# schematic.net
KiCad netlist of a schematic drawn in EasyEDA
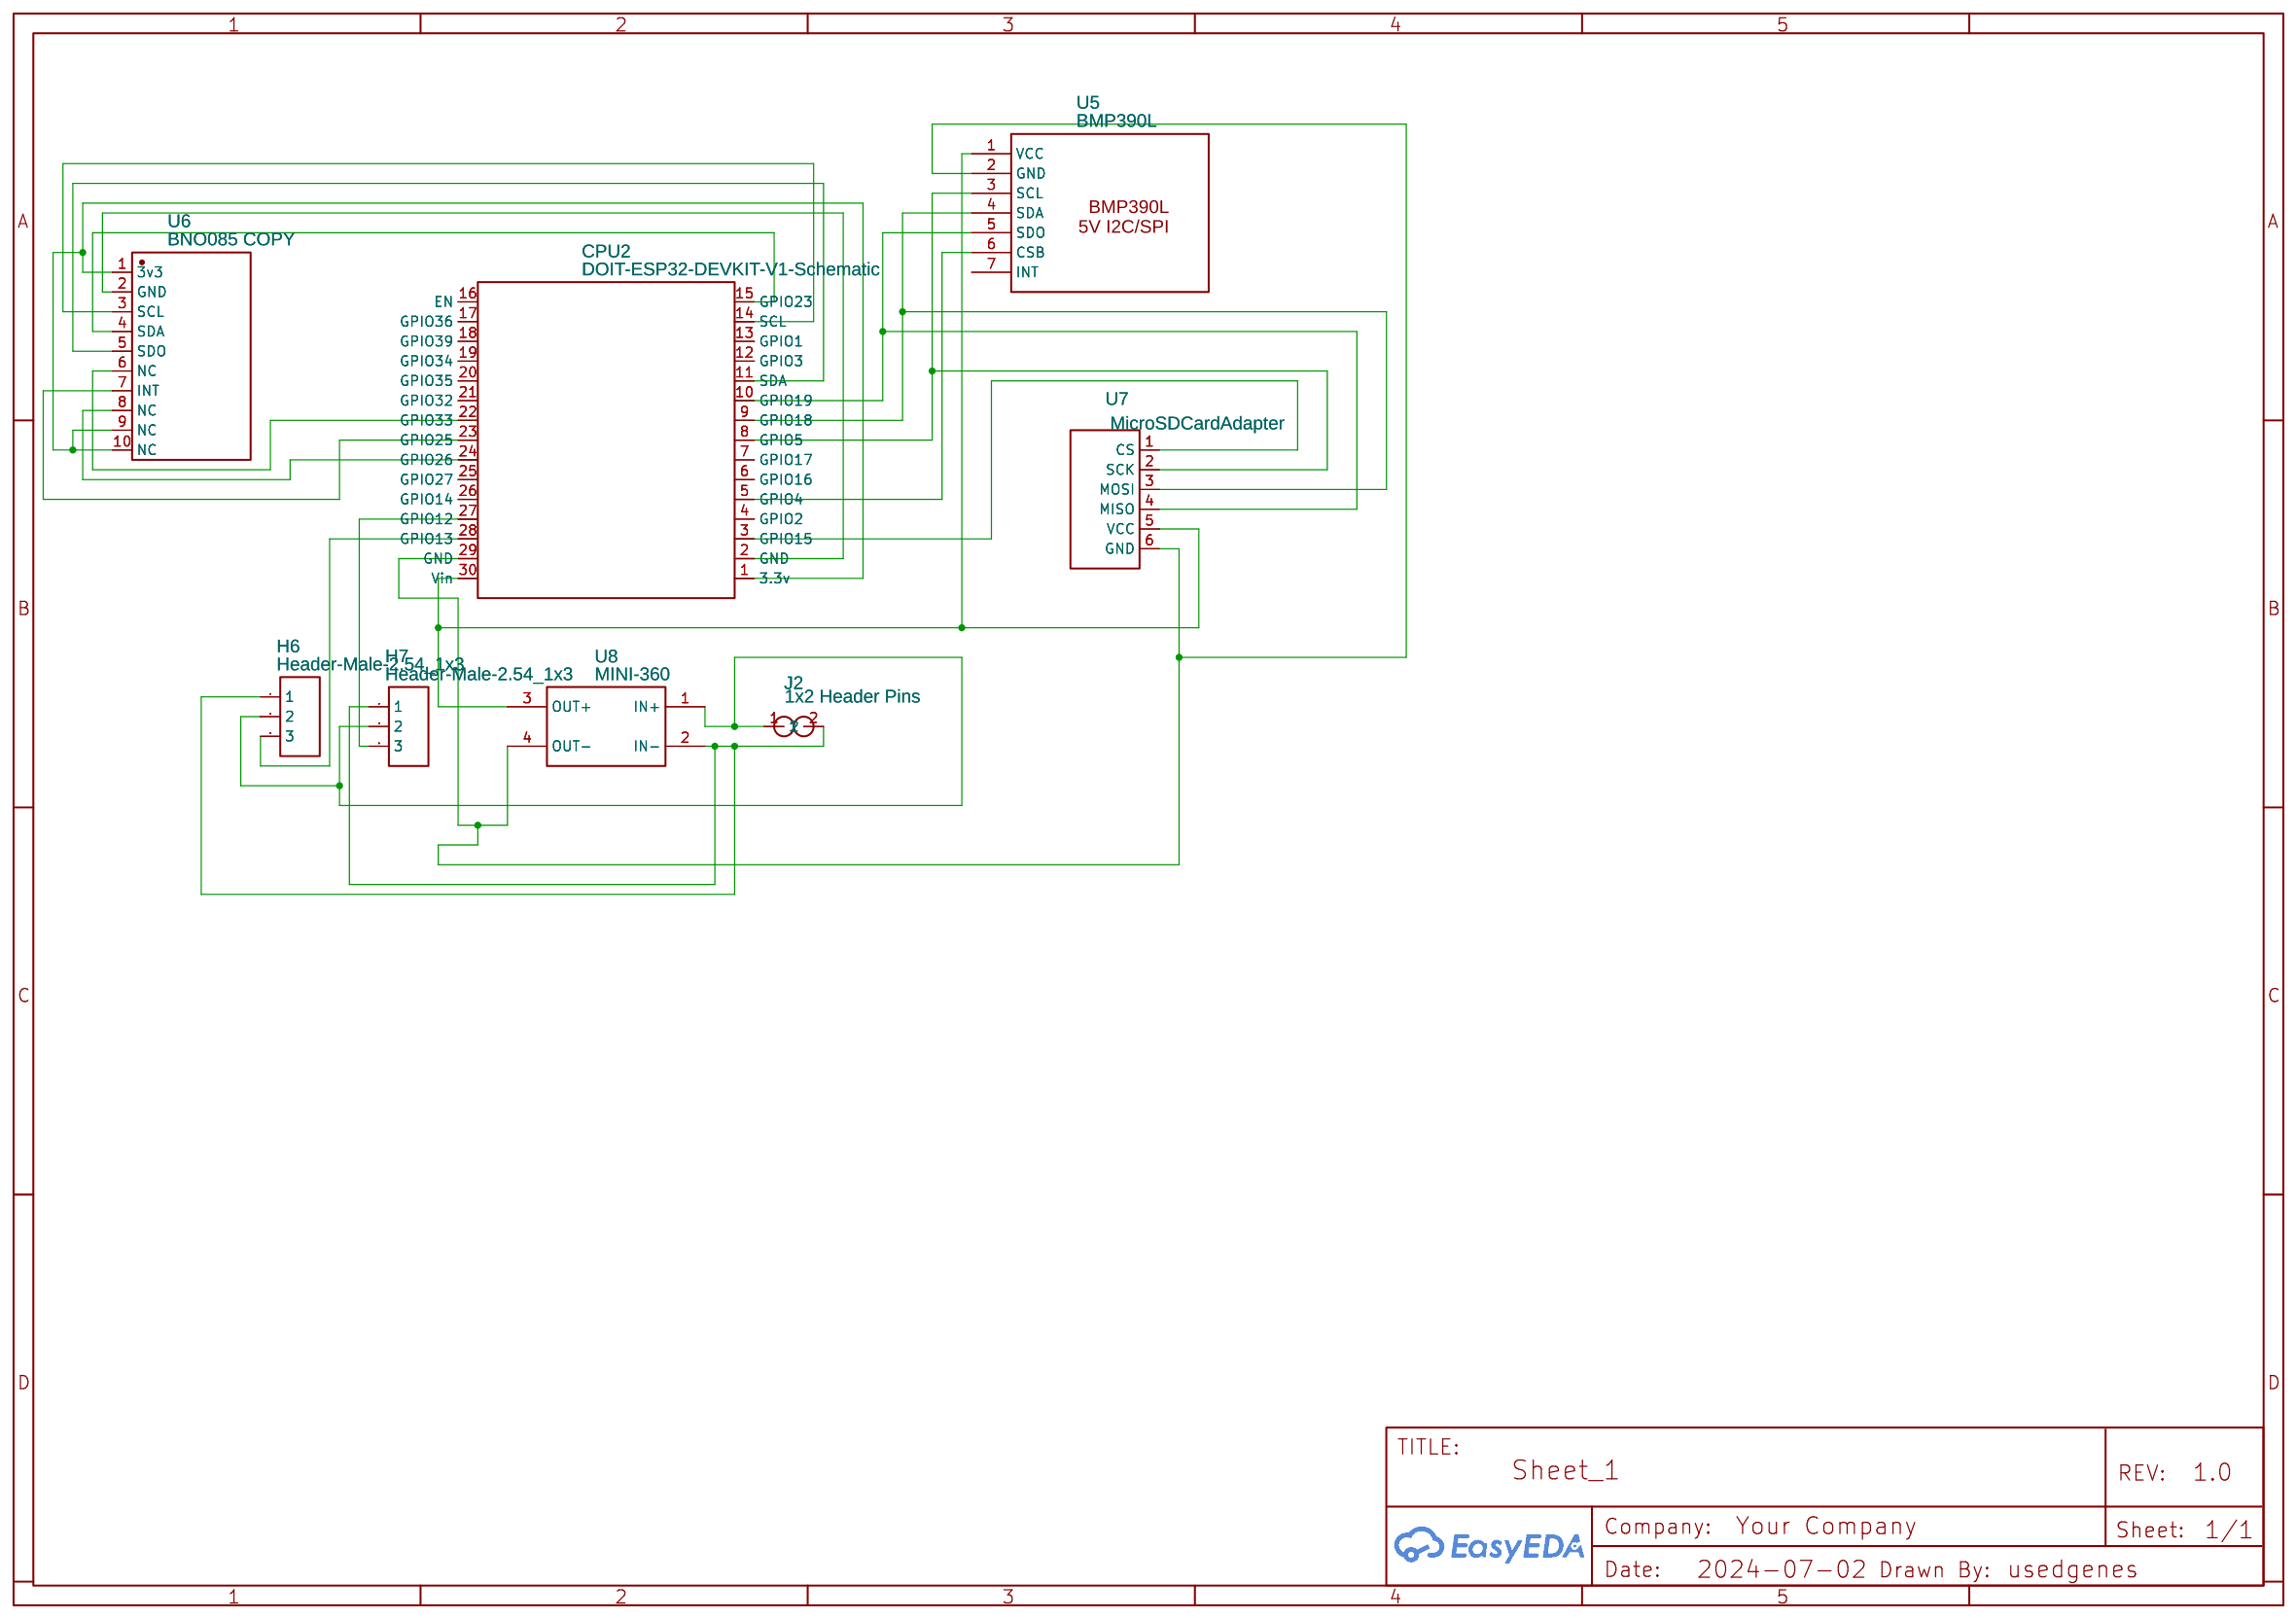
[diagram p0: schematic sheet]

(export (version "E")
  (design (tool "Eeschema 10.0.6"))
  (components
    (comp (ref "CPU2")
      (value "DOIT-ESP32-DEVKIT-V1-Schematic")
      (fields (field (name "Manufacturer Part") "NONE"))
      (libsource (lib "") (part "DOIT-ESP32-DEVKIT-V1-Schematic"))
    )
    (comp (ref "H6")
      (value "Header-Male-2.54_1x3")
      (fields (field (name "Manufacturer Part") "2.54-1*3P针") (field (name "Manufacturer") "BOOMELE(博穆精密)"))
      (libsource (lib "") (part "Header-Male-2.54_1x3"))
    )
    (comp (ref "H7")
      (value "Header-Male-2.54_1x3")
      (fields (field (name "Manufacturer Part") "2.54-1*3P针") (field (name "Manufacturer") "BOOMELE(博穆精密)"))
      (libsource (lib "") (part "Header-Male-2.54_1x3"))
    )
    (comp (ref "J2")
      (value "1x2 Header Pins")
      (fields
        (field (name "Manufacturer Part") "61300211121")
        (field (name "Manufacturer") "Wurth Electronics")
      )
      (libsource (lib "") (part "1x2 Header Pins"))
    )
    (comp (ref "U5")
      (value "BMP390L")
      (fields (field (name "Manufacturer Part") "BME280") (field (name "Manufacturer") "ditmore"))
      (libsource (lib "") (part "BMP390L"))
    )
    (comp (ref "U6")
      (value "BNO085 COPY")
      (fields (field (name "Manufacturer Part") "BNO085") (field (name "Manufacturer") "Slime"))
      (libsource (lib "") (part "BNO085 COPY"))
    )
    (comp (ref "U7") (value "MicroSDCardAdapter") (libsource (lib "") (part "MicroSDCardAdapter")))
    (comp (ref "U8") (value "MINI-360") (libsource (lib "") (part "MINI-360")))
  )
  (nets
    (net (code "1") (name "Net-(CPU2-3.3v)") (class "Default")
      (node (ref "CPU2") (pin "1") (pinfunction "3.3v_1") (pintype "unspecified"))
      (node (ref "U6") (pin "1") (pinfunction "3v3_1") (pintype "unspecified"))
      (node (ref "U6") (pin "10") (pinfunction "NC_10") (pintype "unspecified"))
      (node (ref "U6") (pin "9") (pinfunction "NC_9") (pintype "unspecified"))
    )
    (net (code "2") (name "Net-(CPU2-GPIO4)") (class "Default")
      (node (ref "CPU2") (pin "5") (pinfunction "GPIO4_5") (pintype "unspecified"))
      (node (ref "U5") (pin "6") (pinfunction "CSB_6") (pintype "unspecified"))
    )
    (net (code "3") (name "Net-(CPU2-GPIO5)") (class "Default")
      (node (ref "CPU2") (pin "8") (pinfunction "GPIO5_8") (pintype "unspecified"))
      (node (ref "U5") (pin "3") (pinfunction "SCL_3") (pintype "unspecified"))
      (node (ref "U7") (pin "2") (pinfunction "SCK_2") (pintype "bidirectional"))
    )
    (net (code "4") (name "Net-(CPU2-GPIO12)") (class "Default")
      (node (ref "CPU2") (pin "27") (pinfunction "GPIO12_27") (pintype "unspecified"))
      (node (ref "H7") (pin "3") (pinfunction "3_3") (pintype "input"))
    )
    (net (code "5") (name "Net-(CPU2-GPIO13)") (class "Default")
      (node (ref "CPU2") (pin "28") (pinfunction "GPIO13_28") (pintype "unspecified"))
      (node (ref "H6") (pin "3") (pinfunction "3_3") (pintype "input"))
    )
    (net (code "6") (name "Net-(CPU2-GPIO15)") (class "Default")
      (node (ref "CPU2") (pin "3") (pinfunction "GPIO15_3") (pintype "unspecified"))
      (node (ref "U7") (pin "1") (pinfunction "CS_1") (pintype "bidirectional"))
    )
    (net (code "7") (name "Net-(CPU2-GPIO18)") (class "Default")
      (node (ref "CPU2") (pin "9") (pinfunction "GPIO18_9") (pintype "unspecified"))
      (node (ref "U5") (pin "4") (pinfunction "SDA_4") (pintype "unspecified"))
      (node (ref "U7") (pin "3") (pinfunction "MOSI_3") (pintype "passive"))
    )
    (net (code "8") (name "Net-(CPU2-GPIO19)") (class "Default")
      (node (ref "CPU2") (pin "10") (pinfunction "GPIO19_10") (pintype "unspecified"))
      (node (ref "U5") (pin "5") (pinfunction "SDO_5") (pintype "unspecified"))
      (node (ref "U7") (pin "4") (pinfunction "MISO_4") (pintype "bidirectional"))
    )
    (net (code "9") (name "Net-(CPU2-GPIO23)") (class "Default")
      (node (ref "CPU2") (pin "15") (pinfunction "GPIO23_15") (pintype "unspecified"))
      (node (ref "U6") (pin "4") (pinfunction "SDA_4") (pintype "unspecified"))
    )
    (net (code "10") (name "Net-(CPU2-GPIO25)") (class "Default")
      (node (ref "CPU2") (pin "23") (pinfunction "GPIO25_23") (pintype "unspecified"))
      (node (ref "U6") (pin "7") (pinfunction "INT_7") (pintype "unspecified"))
    )
    (net (code "11") (name "Net-(CPU2-GPIO26)") (class "Default")
      (node (ref "CPU2") (pin "24") (pinfunction "GPIO26_24") (pintype "unspecified"))
      (node (ref "U6") (pin "8") (pinfunction "NC_8") (pintype "unspecified"))
    )
    (net (code "12") (name "Net-(CPU2-GPIO33)") (class "Default")
      (node (ref "CPU2") (pin "22") (pinfunction "GPIO33_22") (pintype "unspecified"))
      (node (ref "U6") (pin "6") (pinfunction "NC_6") (pintype "unspecified"))
    )
    (net (code "13") (name "Net-(CPU2-SCL)") (class "Default")
      (node (ref "CPU2") (pin "14") (pinfunction "SCL_14") (pintype "unspecified"))
      (node (ref "U6") (pin "3") (pinfunction "SCL_3") (pintype "unspecified"))
    )
    (net (code "14") (name "Net-(CPU2-SDA)") (class "Default")
      (node (ref "CPU2") (pin "11") (pinfunction "SDA_11") (pintype "unspecified"))
      (node (ref "U6") (pin "5") (pinfunction "SDO_5") (pintype "unspecified"))
    )
    (net (code "15") (name "Net-(CPU2-Vin)") (class "Default")
      (node (ref "CPU2") (pin "30") (pinfunction "Vin_30") (pintype "unspecified"))
      (node (ref "U5") (pin "1") (pinfunction "VCC_1") (pintype "unspecified"))
      (node (ref "U7") (pin "5") (pinfunction "VCC_5") (pintype "passive"))
      (node (ref "U8") (pin "3") (pinfunction "OUT+_3") (pintype "unspecified"))
    )
    (net (code "16") (name "Net-(U5-GND)") (class "Default")
      (node (ref "CPU2") (pin "29") (pinfunction "GND_29") (pintype "unspecified"))
      (node (ref "U5") (pin "2") (pinfunction "GND_2") (pintype "unspecified"))
      (node (ref "U7") (pin "6") (pinfunction "GND_6") (pintype "passive"))
      (node (ref "U8") (pin "4") (pinfunction "OUT-_4") (pintype "unspecified"))
    )
    (net (code "17") (name "Net-(U6-GND)") (class "Default")
      (node (ref "CPU2") (pin "2") (pinfunction "GND_2") (pintype "unspecified"))
      (node (ref "U6") (pin "2") (pinfunction "GND_2") (pintype "unspecified"))
    )
    (net (code "18") (name "Net-(U8-IN+)") (class "Default")
      (node (ref "H6") (pin "2") (pinfunction "2_2") (pintype "input"))
      (node (ref "H7") (pin "2") (pinfunction "2_2") (pintype "input"))
      (node (ref "J2") (pin "1") (pinfunction "1_1") (pintype "unspecified"))
      (node (ref "U8") (pin "1") (pinfunction "IN+_1") (pintype "unspecified"))
    )
    (net (code "19") (name "Net-(U8-IN-)") (class "Default")
      (node (ref "H6") (pin "1") (pinfunction "1_1") (pintype "input"))
      (node (ref "H7") (pin "1") (pinfunction "1_1") (pintype "input"))
      (node (ref "J2") (pin "2") (pinfunction "2_2") (pintype "unspecified"))
      (node (ref "U8") (pin "2") (pinfunction "IN-_2") (pintype "unspecified"))
    )
    (net (code "20") (name "unconnected-(CPU2-EN-Pad16)") (class "Default")
      (node (ref "CPU2") (pin "16") (pinfunction "EN_16") (pintype "unspecified"))
    )
    (net (code "21") (name "unconnected-(CPU2-GPIO1-Pad13)") (class "Default")
      (node (ref "CPU2") (pin "13") (pinfunction "GPIO1_13") (pintype "unspecified"))
    )
    (net (code "22") (name "unconnected-(CPU2-GPIO2-Pad4)") (class "Default")
      (node (ref "CPU2") (pin "4") (pinfunction "GPIO2_4") (pintype "unspecified"))
    )
    (net (code "23") (name "unconnected-(CPU2-GPIO3-Pad12)") (class "Default")
      (node (ref "CPU2") (pin "12") (pinfunction "GPIO3_12") (pintype "unspecified"))
    )
    (net (code "24") (name "unconnected-(CPU2-GPIO14-Pad26)") (class "Default")
      (node (ref "CPU2") (pin "26") (pinfunction "GPIO14_26") (pintype "unspecified"))
    )
    (net (code "25") (name "unconnected-(CPU2-GPIO16-Pad6)") (class "Default")
      (node (ref "CPU2") (pin "6") (pinfunction "GPIO16_6") (pintype "unspecified"))
    )
    (net (code "26") (name "unconnected-(CPU2-GPIO17-Pad7)") (class "Default")
      (node (ref "CPU2") (pin "7") (pinfunction "GPIO17_7") (pintype "unspecified"))
    )
    (net (code "27") (name "unconnected-(CPU2-GPIO27-Pad25)") (class "Default")
      (node (ref "CPU2") (pin "25") (pinfunction "GPIO27_25") (pintype "unspecified"))
    )
    (net (code "28") (name "unconnected-(CPU2-GPIO32-Pad21)") (class "Default")
      (node (ref "CPU2") (pin "21") (pinfunction "GPIO32_21") (pintype "unspecified"))
    )
    (net (code "29") (name "unconnected-(CPU2-GPIO34-Pad19)") (class "Default")
      (node (ref "CPU2") (pin "19") (pinfunction "GPIO34_19") (pintype "unspecified"))
    )
    (net (code "30") (name "unconnected-(CPU2-GPIO35-Pad20)") (class "Default")
      (node (ref "CPU2") (pin "20") (pinfunction "GPIO35_20") (pintype "unspecified"))
    )
    (net (code "31") (name "unconnected-(CPU2-GPIO36-Pad17)") (class "Default")
      (node (ref "CPU2") (pin "17") (pinfunction "GPIO36_17") (pintype "unspecified"))
    )
    (net (code "32") (name "unconnected-(CPU2-GPIO39-Pad18)") (class "Default")
      (node (ref "CPU2") (pin "18") (pinfunction "GPIO39_18") (pintype "unspecified"))
    )
    (net (code "33") (name "unconnected-(U5-INT-Pad7)") (class "Default")
      (node (ref "U5") (pin "7") (pinfunction "INT_7") (pintype "unspecified"))
    )
  )
)
